# CH32F_V208C-R0.net
KiCad netlist of a schematic drawn in Altium Designer
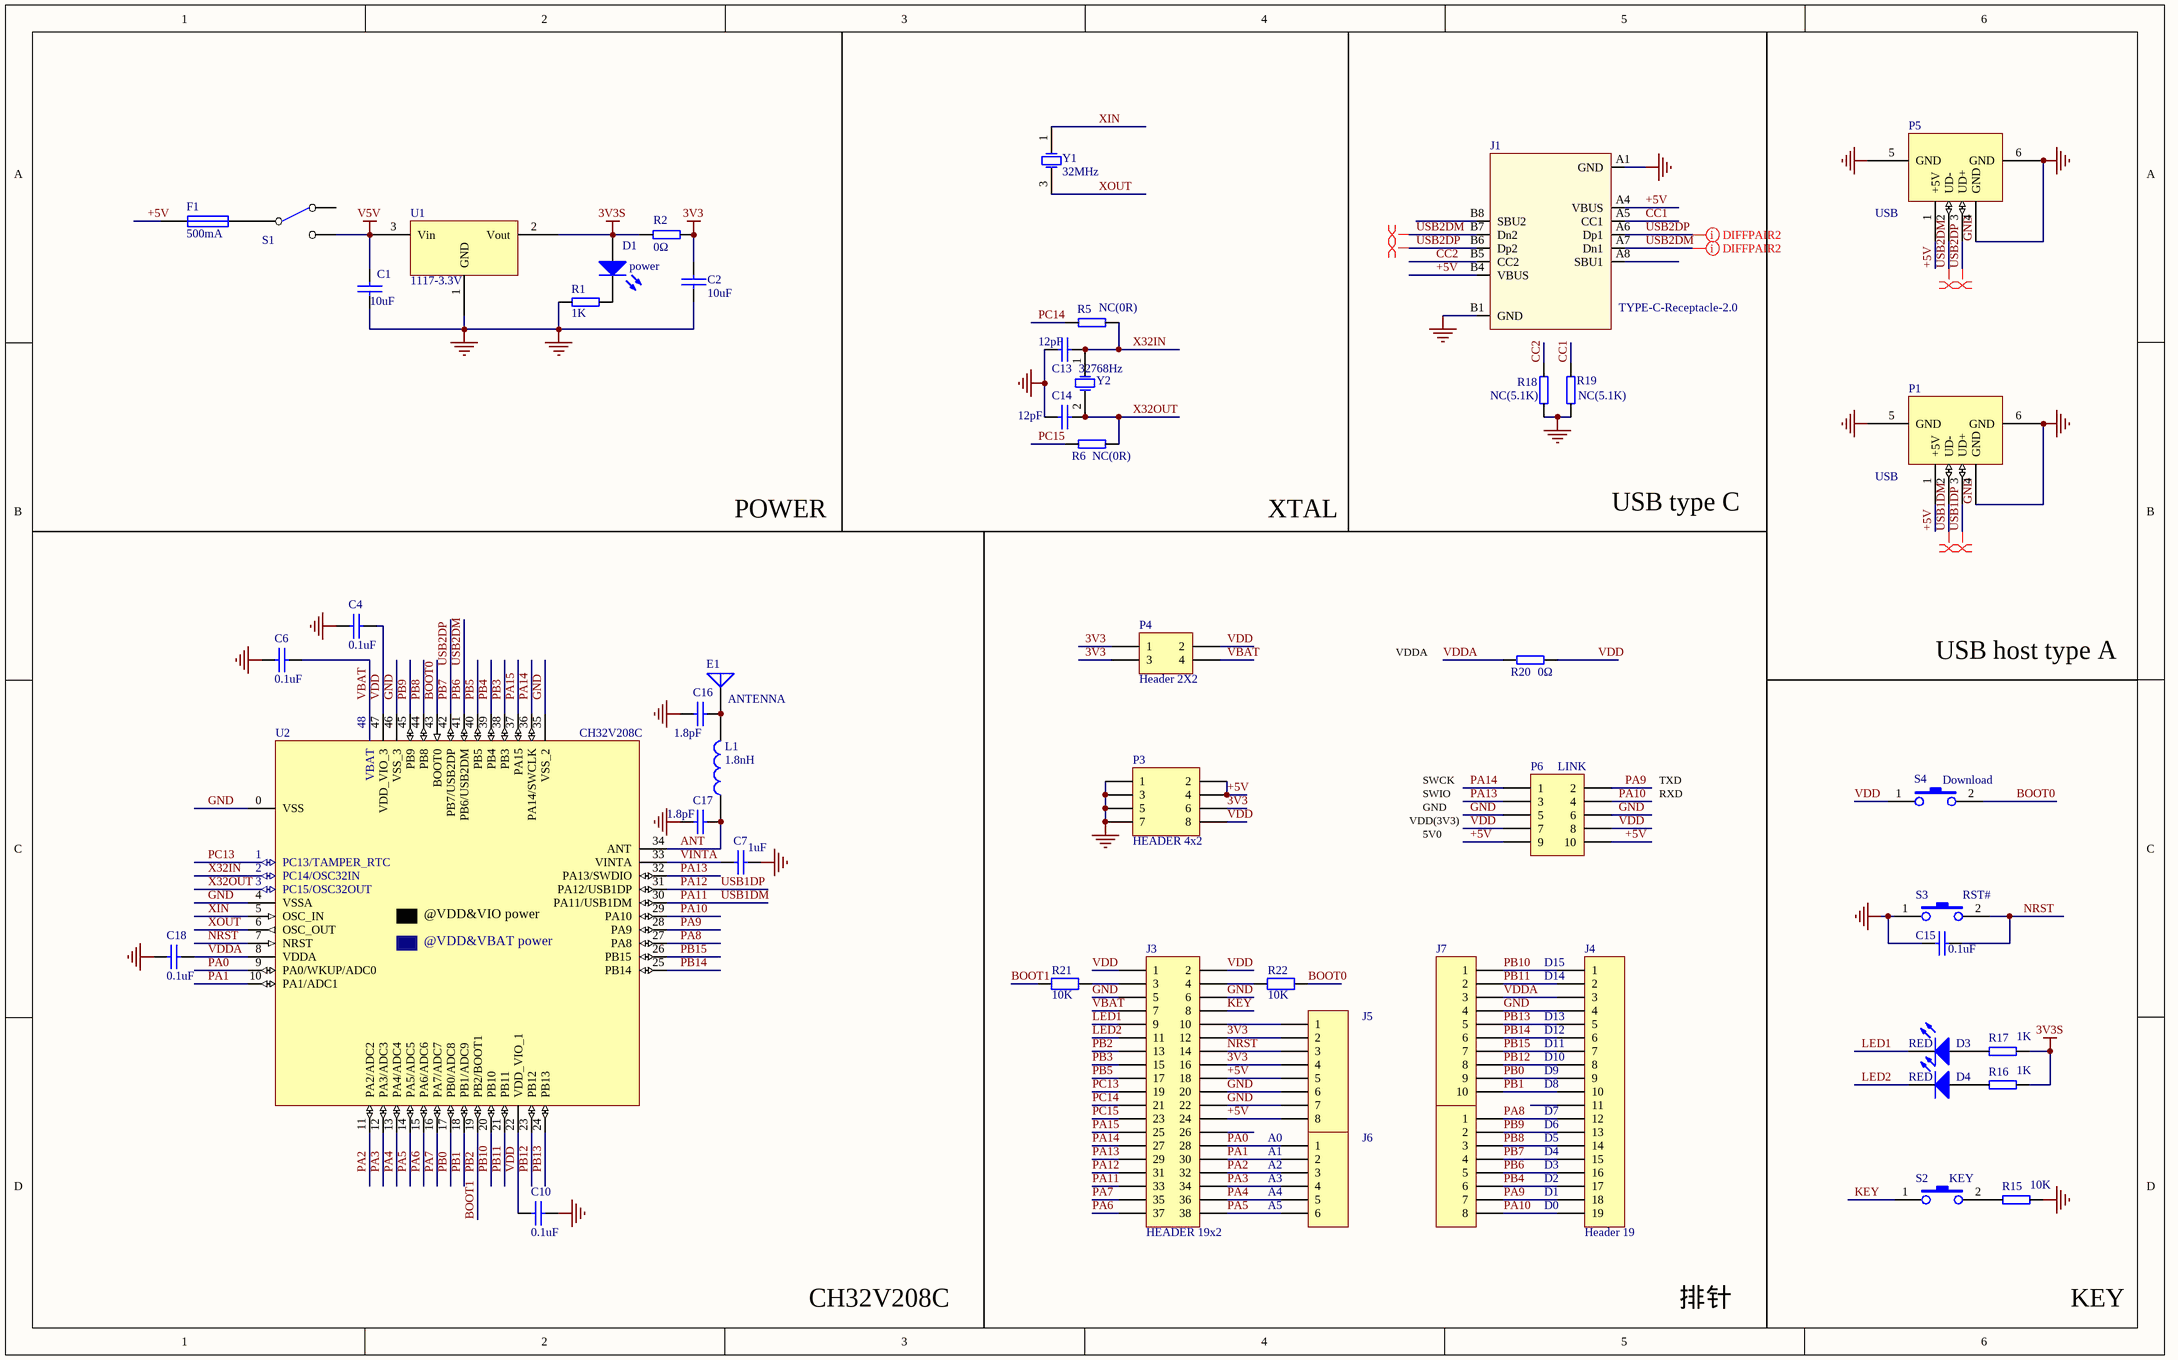
[diagram p0: CH32F&V208C-R0.SchDoc]

(export (version "E")
  (design (tool "Eeschema 10.0.6"))
  (components
    (comp (ref "C1")
      (value "10uF")
      (footprint "3216_C")
      (description "Capacitor")
      (libsource (lib "") (part "CAP_1"))
    )
    (comp (ref "C2")
      (value "10uF")
      (footprint "0603_C")
      (description "Capacitor")
      (libsource (lib "") (part "CAP_1"))
    )
    (comp (ref "C4")
      (value "0.1uF")
      (footprint "0603_C")
      (description "Capacitor")
      (libsource (lib "*") (part "CAP"))
    )
    (comp (ref "C6")
      (value "0.1uF")
      (footprint "0603_C")
      (description "Capacitor")
      (libsource (lib "*") (part "CAP"))
    )
    (comp (ref "C7")
      (value "1uF")
      (footprint "0603_C")
      (description "Capacitor")
      (libsource (lib "*") (part "CAP"))
    )
    (comp (ref "C10")
      (value "0.1uF")
      (footprint "0603_C")
      (description "Capacitor")
      (libsource (lib "*") (part "CAP"))
    )
    (comp (ref "C13")
      (value "12pF")
      (footprint "0603_C")
      (description "Capacitor")
      (libsource (lib "") (part "CAP_1"))
    )
    (comp (ref "C14")
      (value "12pF")
      (footprint "0603_C")
      (description "Capacitor")
      (libsource (lib "") (part "CAP_1"))
    )
    (comp (ref "C15")
      (value "0.1uF")
      (footprint "0603_C")
      (description "Capacitor")
      (libsource (lib "*") (part "CAP"))
    )
    (comp (ref "C16")
      (value "1.8pF")
      (footprint "0603_C")
      (description "Capacitor")
      (libsource (lib "*") (part "CAP"))
    )
    (comp (ref "C17")
      (value "1.8pF")
      (footprint "0603_C")
      (description "Capacitor")
      (libsource (lib "*") (part "CAP"))
    )
    (comp (ref "C18")
      (value "0.1uF")
      (footprint "0603_C")
      (description "Capacitor")
      (libsource (lib "*") (part "CAP"))
    )
    (comp (ref "D1")
      (value "power")
      (footprint "0603+")
      (description "Typical INFRARED GaAs LED")
      (fields (field (name "PUBLISHER") "Altium Limited"))
      (libsource (lib "*") (part "LED0"))
    )
    (comp (ref "D3")
      (value "RED")
      (footprint "0603+")
      (description "Typical INFRARED GaAs LED")
      (fields (field (name "PUBLISHER") "Altium Limited"))
      (libsource (lib "*") (part "LED0"))
    )
    (comp (ref "D4")
      (value "RED")
      (footprint "0603+")
      (description "Typical INFRARED GaAs LED")
      (fields (field (name "PUBLISHER") "Altium Limited"))
      (libsource (lib "*") (part "LED0"))
    )
    (comp (ref "E1")
      (value "ANTENNA")
      (footprint "ANT-F-1-2.4G-1.6mmFR4")
      (description "Generic Antenna")
      (libsource (lib "*") (part "ANTENNA"))
    )
    (comp (ref "F1")
      (value "500mA")
      (footprint "0603")
      (description "Fuse")
      (libsource (lib "wch_sch_others") (part "FUSE1"))
    )
    (comp (ref "J1")
      (value "TYPE-C-Receptacle-2.0")
      (footprint "TYPE-C-Receptacle-2.0")
      (description "Type-C USB2.0 母座")
      (libsource (lib "Miscellaneous SCH Lib") (part "TYPE-C-Receptacle-2.0"))
    )
    (comp (ref "J3")
      (value "HEADER 19x2")
      (footprint "MYPCB:IDC38-2.54MM")
      (description "Header, 19-Pin, Dual row")
      (libsource (lib "wch_sch_others") (part "HEADER 19x2"))
    )
    (comp (ref "J4")
      (value "Header 19")
      (footprint "SIP19-2.54mm")
      (description "Header, 19-Pin")
      (fields (field (name "PUBLISHER") "Altium Limited"))
      (libsource (lib "Miscellaneous Connectors") (part "Header 19"))
    )
    (comp (ref "J5")
      (value "Header 8")
      (footprint "SIP8-2.54mm")
      (description "Header, 8-Pin")
      (fields (field (name "PUBLISHER") "Altium Limited"))
      (libsource (lib "") (part "Header 8_1"))
    )
    (comp (ref "J6")
      (value "Header 6")
      (footprint "SIP6-2.54MM")
      (description "Header, 6-Pin")
      (fields (field (name "PUBLISHER") "Altium Limited"))
      (libsource (lib "Miscellaneous Connectors") (part "Header 6"))
    )
    (comp (ref "J7")
      (value "Header 10")
      (footprint "SIP10-2.54mm")
      (description "Header, 10-Pin")
      (fields (field (name "PUBLISHER") "Altium Limited"))
      (libsource (lib "Miscellaneous Connectors") (part "Header 10"))
    )
    (comp (ref "J8")
      (value "Header 8")
      (footprint "SIP8-2.54mm")
      (description "Header, 8-Pin")
      (fields (field (name "PUBLISHER") "Altium Limited"))
      (libsource (lib "Miscellaneous Connectors") (part "Header 8"))
    )
    (comp (ref "L1") (value "1.8nH") (footprint "0603") (libsource (lib "*") (part "INDUCTOR")))
    (comp (ref "P1")
      (value "USB")
      (footprint "USBAF")
      (description "USB Port")
      (libsource (lib "*") (part "USB"))
    )
    (comp (ref "P3")
      (value "HEADER 4x2")
      (footprint "MYPCB:IDC8-2.54mm")
      (description "Header, 4-Pin, Dual row")
      (libsource (lib "wch_sch_others") (part "HEADER 4x2"))
    )
    (comp (ref "P4")
      (value "Header 2X2")
      (footprint "IDC4-2.54mm")
      (description "Header, 2-Pin, Dual row")
      (fields (field (name "PUBLISHER") "Altium Limited"))
      (libsource (lib "Miscellaneous Connectors") (part "Header 2X2"))
    )
    (comp (ref "P5")
      (value "USB")
      (footprint "USBAF")
      (description "USB Port")
      (libsource (lib "*") (part "USB"))
    )
    (comp (ref "P6")
      (value "LINK")
      (footprint "IDC10-2.54mm")
      (description "Header, 5-Pin, Dual row, Right Angle")
      (fields (field (name "PUBLISHER") "Altium Limited"))
      (libsource (lib "Miscellaneous Connectors") (part "Header 5X2H"))
    )
    (comp (ref "R1") (value "1K") (footprint "0603") (libsource (lib "wch_sch_others") (part "RES")))
    (comp (ref "R2") (value "0Ω") (footprint "0603") (libsource (lib "wch_sch_others") (part "RES")))
    (comp (ref "R5") (value "NC(0R)") (footprint "0603") (libsource (lib "wch_sch_others") (part "RES")))
    (comp (ref "R6") (value "NC(0R)") (footprint "0603") (libsource (lib "wch_sch_others") (part "RES")))
    (comp (ref "R15") (value "10K") (footprint "0603") (libsource (lib "wch_sch_others") (part "RES")))
    (comp (ref "R16") (value "1K") (footprint "0603") (libsource (lib "wch_sch_others") (part "RES")))
    (comp (ref "R17") (value "1K") (footprint "0603") (libsource (lib "wch_sch_others") (part "RES")))
    (comp (ref "R18") (value "NC(5.1K)") (footprint "0603") (libsource (lib "wch_sch_others") (part "RES")))
    (comp (ref "R19") (value "NC(5.1K)") (footprint "0603") (libsource (lib "wch_sch_others") (part "RES")))
    (comp (ref "R20") (value "0Ω") (footprint "0603") (libsource (lib "*") (part "R")))
    (comp (ref "R21")
      (value "10K")
      (footprint "0603")
      (description "Resistor")
      (libsource (lib "Miscellaneous Devices") (part "Res2"))
    )
    (comp (ref "R22")
      (value "10K")
      (footprint "0603")
      (description "Resistor")
      (libsource (lib "Miscellaneous Devices") (part "Res2"))
    )
    (comp (ref "S1") (value "SW SPDT") (footprint "SW1") (libsource (lib "*") (part "SW SPDT")))
    (comp (ref "S2")
      (value "KEY")
      (footprint "SMD_6.1x3.65x2.5mm-KEY")
      (libsource (lib "wch_sch_others") (part "KEY1"))
    )
    (comp (ref "S3")
      (value "RST#")
      (footprint "SMD_6.1x3.65x2.5mm-KEY")
      (libsource (lib "wch_sch_others") (part "KEY1"))
    )
    (comp (ref "S4")
      (value "Download")
      (footprint "SMD_6.1x3.65x2.5mm-KEY")
      (libsource (lib "wch_sch_others") (part "KEY1"))
    )
    (comp (ref "U1")
      (value "1117-3.3V")
      (footprint "SOT-223")
      (libsource (lib "wch_sch_others") (part "1117-3.3V"))
    )
    (comp (ref "U2")
      (value "CH32V208C")
      (footprint "QFN48_5x5")
      (description "RISC-V BLE5.3 MCU, 10M Ethernet, 2*USB, CAN")
      (libsource (lib "CHXXX") (part "CH32V208C"))
    )
    (comp (ref "Y1")
      (value "32MHz")
      (footprint "XT3225")
      (description "Crystal Oscillator")
      (fields (field (name "PUBLISHER") "Altium Limited"))
      (libsource (lib "") (part "XTAL_1"))
    )
    (comp (ref "Y2")
      (value "32768Hz")
      (footprint "FC-135")
      (description "Crystal Oscillator")
      (fields (field (name "PUBLISHER") "Altium Limited"))
      (libsource (lib "*") (part "XTAL"))
    )
  )
  (nets
    (net (code "1") (name "/+5V") (class "Default")
      (node (ref "F1") (pin "1") (pinfunction "1_1") (pintype "passive"))
      (node (ref "J1") (pin "A4") (pinfunction "VBUS_A4") (pintype "passive"))
      (node (ref "J1") (pin "B4") (pinfunction "VBUS_B4") (pintype "passive"))
      (node (ref "J3") (pin "18") (pinfunction "18_18") (pintype "passive"))
      (node (ref "J3") (pin "24") (pinfunction "24_24") (pintype "passive"))
      (node (ref "J5") (pin "5") (pinfunction "5_5") (pintype "passive"))
      (node (ref "J5") (pin "8") (pinfunction "8_8") (pintype "passive"))
      (node (ref "P1") (pin "1") (pinfunction "+5V_1") (pintype "power_in"))
      (node (ref "P3") (pin "2") (pinfunction "2_2") (pintype "passive"))
      (node (ref "P3") (pin "4") (pinfunction "4_4") (pintype "passive"))
      (node (ref "P5") (pin "1") (pinfunction "+5V_1") (pintype "power_in"))
      (node (ref "P6") (pin "10") (pinfunction "10_10") (pintype "passive"))
      (node (ref "P6") (pin "9") (pinfunction "9_9") (pintype "passive"))
    )
    (net (code "2") (name "/ANT") (class "Default")
      (node (ref "C17") (pin "2") (pinfunction "2_2") (pintype "passive"))
      (node (ref "L1") (pin "1") (pinfunction "1_1") (pintype "passive"))
      (node (ref "U2") (pin "34") (pinfunction "ANT_34") (pintype "power_in"))
    )
    (net (code "3") (name "/BOOT0") (class "Default")
      (node (ref "R22") (pin "2") (pinfunction "2_2") (pintype "passive"))
      (node (ref "S4") (pin "2") (pinfunction "2_2") (pintype "passive"))
      (node (ref "U2") (pin "43") (pinfunction "BOOT0_43") (pintype "input"))
    )
    (net (code "4") (name "/BOOT1") (class "Default")
      (node (ref "J3") (pin "13") (pinfunction "13_13") (pintype "passive"))
      (node (ref "R21") (pin "1") (pinfunction "1_1") (pintype "passive"))
      (node (ref "U2") (pin "19") (pinfunction "PB2/BOOT1_19") (pintype "bidirectional"))
    )
    (net (code "5") (name "/CC1") (class "Default")
      (node (ref "J1") (pin "A5") (pinfunction "CC1_A5") (pintype "passive"))
      (node (ref "R19") (pin "1") (pintype "passive"))
    )
    (net (code "6") (name "/CC2") (class "Default")
      (node (ref "J1") (pin "B5") (pinfunction "CC2_B5") (pintype "passive"))
      (node (ref "R18") (pin "1") (pintype "passive"))
    )
    (net (code "7") (name "/KEY") (class "Default")
      (node (ref "J3") (pin "8") (pinfunction "8_8") (pintype "passive"))
      (node (ref "S2") (pin "1") (pinfunction "1_1") (pintype "passive"))
    )
    (net (code "8") (name "/LED1") (class "Default")
      (node (ref "D3") (pin "2") (pinfunction "K_2") (pintype "passive"))
      (node (ref "J3") (pin "9") (pinfunction "9_9") (pintype "passive"))
    )
    (net (code "9") (name "/LED2") (class "Default")
      (node (ref "D4") (pin "2") (pinfunction "K_2") (pintype "passive"))
      (node (ref "J3") (pin "11") (pinfunction "11_11") (pintype "passive"))
    )
    (net (code "10") (name "/NRST") (class "Default")
      (node (ref "C15") (pin "2") (pinfunction "2_2") (pintype "passive"))
      (node (ref "J3") (pin "14") (pinfunction "14_14") (pintype "passive"))
      (node (ref "J5") (pin "3") (pinfunction "3_3") (pintype "passive"))
      (node (ref "S3") (pin "2") (pinfunction "2_2") (pintype "passive"))
      (node (ref "U2") (pin "7") (pinfunction "NRST_7") (pintype "input"))
    )
    (net (code "11") (name "/PA0") (class "Default")
      (node (ref "J3") (pin "28") (pinfunction "28_28") (pintype "passive"))
      (node (ref "J6") (pin "1") (pinfunction "1_1") (pintype "passive"))
      (node (ref "U2") (pin "9") (pinfunction "PA0/WKUP/ADC0_9") (pintype "bidirectional"))
    )
    (net (code "12") (name "/PA1") (class "Default")
      (node (ref "J3") (pin "30") (pinfunction "30_30") (pintype "passive"))
      (node (ref "J6") (pin "2") (pinfunction "2_2") (pintype "passive"))
      (node (ref "U2") (pin "10") (pinfunction "PA1/ADC1_10") (pintype "bidirectional"))
    )
    (net (code "13") (name "/PA2") (class "Default")
      (node (ref "J3") (pin "32") (pinfunction "32_32") (pintype "passive"))
      (node (ref "J6") (pin "3") (pinfunction "3_3") (pintype "passive"))
      (node (ref "U2") (pin "11") (pinfunction "PA2/ADC2_11") (pintype "bidirectional"))
    )
    (net (code "14") (name "/PA3") (class "Default")
      (node (ref "J3") (pin "34") (pinfunction "34_34") (pintype "passive"))
      (node (ref "J6") (pin "4") (pinfunction "4_4") (pintype "passive"))
      (node (ref "U2") (pin "12") (pinfunction "PA3/ADC3_12") (pintype "bidirectional"))
    )
    (net (code "15") (name "/PA4") (class "Default")
      (node (ref "J3") (pin "36") (pinfunction "36_36") (pintype "passive"))
      (node (ref "J6") (pin "5") (pinfunction "5_5") (pintype "passive"))
      (node (ref "U2") (pin "13") (pinfunction "PA4/ADC4_13") (pintype "bidirectional"))
    )
    (net (code "16") (name "/PA5") (class "Default")
      (node (ref "J3") (pin "38") (pinfunction "38_38") (pintype "passive"))
      (node (ref "J6") (pin "6") (pinfunction "6_6") (pintype "passive"))
      (node (ref "U2") (pin "14") (pinfunction "PA5/ADC5_14") (pintype "bidirectional"))
    )
    (net (code "17") (name "/PA6") (class "Default")
      (node (ref "J3") (pin "37") (pinfunction "37_37") (pintype "passive"))
      (node (ref "U2") (pin "15") (pinfunction "PA6/ADC6_15") (pintype "bidirectional"))
    )
    (net (code "18") (name "/PA7") (class "Default")
      (node (ref "J3") (pin "35") (pinfunction "35_35") (pintype "passive"))
      (node (ref "U2") (pin "16") (pinfunction "PA7/ADC7_16") (pintype "bidirectional"))
    )
    (net (code "19") (name "/PA8") (class "Default")
      (node (ref "J4") (pin "12") (pinfunction "12_12") (pintype "passive"))
      (node (ref "J8") (pin "1") (pinfunction "1_1") (pintype "passive"))
      (node (ref "U2") (pin "27") (pinfunction "PA8_27") (pintype "bidirectional"))
    )
    (net (code "20") (name "/PA9") (class "Default")
      (node (ref "J4") (pin "18") (pinfunction "18_18") (pintype "passive"))
      (node (ref "J8") (pin "7") (pinfunction "7_7") (pintype "passive"))
      (node (ref "P6") (pin "2") (pinfunction "2_2") (pintype "passive"))
      (node (ref "U2") (pin "28") (pinfunction "PA9_28") (pintype "bidirectional"))
    )
    (net (code "21") (name "/PA10") (class "Default")
      (node (ref "J4") (pin "19") (pinfunction "19_19") (pintype "passive"))
      (node (ref "J8") (pin "8") (pinfunction "8_8") (pintype "passive"))
      (node (ref "P6") (pin "4") (pinfunction "4_4") (pintype "passive"))
      (node (ref "U2") (pin "29") (pinfunction "PA10_29") (pintype "bidirectional"))
    )
    (net (code "22") (name "/PA11") (class "Default")
      (node (ref "J3") (pin "33") (pinfunction "33_33") (pintype "passive"))
      (node (ref "P1") (pin "2") (pinfunction "UD-_2") (pintype "bidirectional"))
      (node (ref "U2") (pin "30") (pinfunction "PA11/USB1DM_30") (pintype "bidirectional"))
    )
    (net (code "23") (name "/PA12") (class "Default")
      (node (ref "J3") (pin "31") (pinfunction "31_31") (pintype "passive"))
      (node (ref "P1") (pin "3") (pinfunction "UD+_3") (pintype "bidirectional"))
      (node (ref "U2") (pin "31") (pinfunction "PA12/USB1DP_31") (pintype "bidirectional"))
    )
    (net (code "24") (name "/PA13") (class "Default")
      (node (ref "J3") (pin "29") (pinfunction "29_29") (pintype "passive"))
      (node (ref "P6") (pin "3") (pinfunction "3_3") (pintype "passive"))
      (node (ref "U2") (pin "32") (pinfunction "PA13/SWDIO_32") (pintype "bidirectional"))
    )
    (net (code "25") (name "/PA14") (class "Default")
      (node (ref "J3") (pin "27") (pinfunction "27_27") (pintype "passive"))
      (node (ref "P6") (pin "1") (pinfunction "1_1") (pintype "passive"))
      (node (ref "U2") (pin "36") (pinfunction "PA14/SWCLK_36") (pintype "bidirectional"))
    )
    (net (code "26") (name "/PA15") (class "Default")
      (node (ref "J3") (pin "25") (pinfunction "25_25") (pintype "passive"))
      (node (ref "U2") (pin "37") (pinfunction "PA15_37") (pintype "bidirectional"))
    )
    (net (code "27") (name "/PB0") (class "Default")
      (node (ref "J4") (pin "9") (pinfunction "9_9") (pintype "passive"))
      (node (ref "J7") (pin "9") (pinfunction "9_9") (pintype "passive"))
      (node (ref "U2") (pin "17") (pinfunction "PB0/ADC8_17") (pintype "bidirectional"))
    )
    (net (code "28") (name "/PB1") (class "Default")
      (node (ref "J4") (pin "10") (pinfunction "10_10") (pintype "passive"))
      (node (ref "J7") (pin "10") (pinfunction "10_10") (pintype "passive"))
      (node (ref "U2") (pin "18") (pinfunction "PB1/ADC9_18") (pintype "bidirectional"))
    )
    (net (code "29") (name "/PB3") (class "Default")
      (node (ref "J3") (pin "15") (pinfunction "15_15") (pintype "passive"))
      (node (ref "U2") (pin "38") (pinfunction "PB3_38") (pintype "bidirectional"))
    )
    (net (code "30") (name "/PB4") (class "Default")
      (node (ref "J4") (pin "17") (pinfunction "17_17") (pintype "passive"))
      (node (ref "J8") (pin "6") (pinfunction "6_6") (pintype "passive"))
      (node (ref "U2") (pin "39") (pinfunction "PB4_39") (pintype "bidirectional"))
    )
    (net (code "31") (name "/PB5") (class "Default")
      (node (ref "J3") (pin "17") (pinfunction "17_17") (pintype "passive"))
      (node (ref "U2") (pin "40") (pinfunction "PB5_40") (pintype "bidirectional"))
    )
    (net (code "32") (name "/PB6") (class "Default")
      (node (ref "J1") (pin "A7") (pinfunction "Dn1_A7") (pintype "passive"))
      (node (ref "J1") (pin "B7") (pinfunction "Dn2_B7") (pintype "passive"))
      (node (ref "J4") (pin "16") (pinfunction "16_16") (pintype "passive"))
      (node (ref "J8") (pin "5") (pinfunction "5_5") (pintype "passive"))
      (node (ref "P5") (pin "2") (pinfunction "UD-_2") (pintype "bidirectional"))
      (node (ref "U2") (pin "41") (pinfunction "PB6/USB2DM_41") (pintype "bidirectional"))
    )
    (net (code "33") (name "/PB7") (class "Default")
      (node (ref "J1") (pin "A6") (pinfunction "Dp1_A6") (pintype "passive"))
      (node (ref "J1") (pin "B6") (pinfunction "Dp2_B6") (pintype "passive"))
      (node (ref "J4") (pin "15") (pinfunction "15_15") (pintype "passive"))
      (node (ref "J8") (pin "4") (pinfunction "4_4") (pintype "passive"))
      (node (ref "P5") (pin "3") (pinfunction "UD+_3") (pintype "bidirectional"))
      (node (ref "U2") (pin "42") (pinfunction "PB7/USB2DP_42") (pintype "bidirectional"))
    )
    (net (code "34") (name "/PB8") (class "Default")
      (node (ref "J4") (pin "14") (pinfunction "14_14") (pintype "passive"))
      (node (ref "J8") (pin "3") (pinfunction "3_3") (pintype "passive"))
      (node (ref "U2") (pin "44") (pinfunction "PB8_44") (pintype "bidirectional"))
    )
    (net (code "35") (name "/PB9") (class "Default")
      (node (ref "J4") (pin "13") (pinfunction "13_13") (pintype "passive"))
      (node (ref "J8") (pin "2") (pinfunction "2_2") (pintype "passive"))
      (node (ref "U2") (pin "45") (pinfunction "PB9_45") (pintype "bidirectional"))
    )
    (net (code "36") (name "/PB10") (class "Default")
      (node (ref "J4") (pin "1") (pinfunction "1_1") (pintype "passive"))
      (node (ref "J7") (pin "1") (pinfunction "1_1") (pintype "passive"))
      (node (ref "U2") (pin "20") (pinfunction "PB10_20") (pintype "bidirectional"))
    )
    (net (code "37") (name "/PB11") (class "Default")
      (node (ref "J4") (pin "2") (pinfunction "2_2") (pintype "passive"))
      (node (ref "J7") (pin "2") (pinfunction "2_2") (pintype "passive"))
      (node (ref "U2") (pin "21") (pinfunction "PB11_21") (pintype "bidirectional"))
    )
    (net (code "38") (name "/PB12") (class "Default")
      (node (ref "J4") (pin "8") (pinfunction "8_8") (pintype "passive"))
      (node (ref "J7") (pin "8") (pinfunction "8_8") (pintype "passive"))
      (node (ref "U2") (pin "23") (pinfunction "PB12_23") (pintype "bidirectional"))
    )
    (net (code "39") (name "/PB13") (class "Default")
      (node (ref "J4") (pin "5") (pinfunction "5_5") (pintype "passive"))
      (node (ref "J7") (pin "5") (pinfunction "5_5") (pintype "passive"))
      (node (ref "U2") (pin "24") (pinfunction "PB13_24") (pintype "bidirectional"))
    )
    (net (code "40") (name "/PB14") (class "Default")
      (node (ref "J4") (pin "6") (pinfunction "6_6") (pintype "passive"))
      (node (ref "J7") (pin "6") (pinfunction "6_6") (pintype "passive"))
      (node (ref "U2") (pin "25") (pinfunction "PB14_25") (pintype "bidirectional"))
    )
    (net (code "41") (name "/PB15") (class "Default")
      (node (ref "J4") (pin "7") (pinfunction "7_7") (pintype "passive"))
      (node (ref "J7") (pin "7") (pinfunction "7_7") (pintype "passive"))
      (node (ref "U2") (pin "26") (pinfunction "PB15_26") (pintype "bidirectional"))
    )
    (net (code "42") (name "/PC13") (class "Default")
      (node (ref "J3") (pin "19") (pinfunction "19_19") (pintype "passive"))
      (node (ref "U2") (pin "1") (pinfunction "PC13/TAMPER_RTC_1") (pintype "bidirectional"))
    )
    (net (code "43") (name "/PC14") (class "Default")
      (node (ref "J3") (pin "21") (pinfunction "21_21") (pintype "passive"))
      (node (ref "R5") (pin "1") (pintype "passive"))
    )
    (net (code "44") (name "/PC15") (class "Default")
      (node (ref "J3") (pin "23") (pinfunction "23_23") (pintype "passive"))
      (node (ref "R6") (pin "1") (pintype "passive"))
    )
    (net (code "45") (name "/VBAT") (class "Default")
      (node (ref "C6") (pin "1") (pinfunction "1_1") (pintype "passive"))
      (node (ref "J3") (pin "7") (pinfunction "7_7") (pintype "passive"))
      (node (ref "P4") (pin "4") (pinfunction "4_4") (pintype "passive"))
      (node (ref "U2") (pin "48") (pinfunction "VBAT_48") (pintype "power_in"))
    )
    (net (code "46") (name "/VDD") (class "Default")
      (node (ref "C10") (pin "2") (pinfunction "2_2") (pintype "passive"))
      (node (ref "C4") (pin "1") (pinfunction "1_1") (pintype "passive"))
      (node (ref "J3") (pin "1") (pinfunction "1_1") (pintype "passive"))
      (node (ref "J3") (pin "2") (pinfunction "2_2") (pintype "passive"))
      (node (ref "P3") (pin "8") (pinfunction "8_8") (pintype "passive"))
      (node (ref "P4") (pin "2") (pinfunction "2_2") (pintype "passive"))
      (node (ref "P6") (pin "7") (pinfunction "7_7") (pintype "passive"))
      (node (ref "P6") (pin "8") (pinfunction "8_8") (pintype "passive"))
      (node (ref "R20") (pin "1") (pinfunction "1_1") (pintype "passive"))
      (node (ref "S4") (pin "1") (pinfunction "1_1") (pintype "passive"))
      (node (ref "U2") (pin "22") (pinfunction "VDD_VIO_1_22") (pintype "power_in"))
      (node (ref "U2") (pin "47") (pinfunction "VDD_VIO_3_47") (pintype "power_in"))
    )
    (net (code "47") (name "/VDDA") (class "Default")
      (node (ref "C18") (pin "1") (pinfunction "1_1") (pintype "passive"))
      (node (ref "J4") (pin "3") (pinfunction "3_3") (pintype "passive"))
      (node (ref "J7") (pin "3") (pinfunction "3_3") (pintype "passive"))
      (node (ref "R20") (pin "2") (pinfunction "2_2") (pintype "passive"))
      (node (ref "U2") (pin "8") (pinfunction "VDDA_8") (pintype "power_in"))
    )
    (net (code "48") (name "/VINTA") (class "Default")
      (node (ref "C7") (pin "1") (pinfunction "1_1") (pintype "passive"))
      (node (ref "U2") (pin "33") (pinfunction "VINTA_33") (pintype "power_in"))
    )
    (net (code "49") (name "/X32IN") (class "Default")
      (node (ref "C13") (pin "2") (pinfunction "2_2") (pintype "passive"))
      (node (ref "R5") (pin "2") (pintype "passive"))
      (node (ref "U2") (pin "2") (pinfunction "PC14/OSC32IN_2") (pintype "bidirectional"))
      (node (ref "Y2") (pin "1") (pinfunction "OSC1_1") (pintype "passive"))
    )
    (net (code "50") (name "/X32OUT") (class "Default")
      (node (ref "C14") (pin "2") (pinfunction "2_2") (pintype "passive"))
      (node (ref "R6") (pin "2") (pintype "passive"))
      (node (ref "U2") (pin "3") (pinfunction "PC15/OSC32OUT_3") (pintype "bidirectional"))
      (node (ref "Y2") (pin "2") (pinfunction "OSC2_2") (pintype "passive"))
    )
    (net (code "51") (name "/XIN") (class "Default")
      (node (ref "U2") (pin "5") (pinfunction "OSC_IN_5") (pintype "input"))
      (node (ref "Y1") (pin "1") (pinfunction "OSC1_1") (pintype "passive"))
    )
    (net (code "52") (name "/XOUT") (class "Default")
      (node (ref "U2") (pin "6") (pinfunction "OSC_OUT_6") (pintype "output"))
      (node (ref "Y1") (pin "3") (pinfunction "OSC2_3") (pintype "passive"))
    )
    (net (code "53") (name "3V3") (class "Default")
      (node (ref "C2") (pin "1") (pinfunction "1_1") (pintype "passive"))
      (node (ref "J3") (pin "12") (pinfunction "12_12") (pintype "passive"))
      (node (ref "J3") (pin "16") (pinfunction "16_16") (pintype "passive"))
      (node (ref "J5") (pin "2") (pinfunction "2_2") (pintype "passive"))
      (node (ref "J5") (pin "4") (pinfunction "4_4") (pintype "passive"))
      (node (ref "P3") (pin "6") (pinfunction "6_6") (pintype "passive"))
      (node (ref "P4") (pin "1") (pinfunction "1_1") (pintype "passive"))
      (node (ref "P4") (pin "3") (pinfunction "3_3") (pintype "passive"))
      (node (ref "R2") (pin "1") (pintype "passive"))
    )
    (net (code "54") (name "3V3S") (class "Default")
      (node (ref "D1") (pin "1") (pinfunction "A_1") (pintype "passive"))
      (node (ref "R16") (pin "1") (pintype "passive"))
      (node (ref "R17") (pin "1") (pintype "passive"))
      (node (ref "R2") (pin "2") (pintype "passive"))
      (node (ref "U1") (pin "2") (pinfunction "Vout_2") (pintype "passive"))
    )
    (net (code "55") (name "GND") (class "Default")
      (node (ref "C1") (pin "2") (pinfunction "2_2") (pintype "passive"))
      (node (ref "C10") (pin "1") (pinfunction "1_1") (pintype "passive"))
      (node (ref "C13") (pin "1") (pinfunction "1_1") (pintype "passive"))
      (node (ref "C14") (pin "1") (pinfunction "1_1") (pintype "passive"))
      (node (ref "C15") (pin "1") (pinfunction "1_1") (pintype "passive"))
      (node (ref "C16") (pin "1") (pinfunction "1_1") (pintype "passive"))
      (node (ref "C17") (pin "1") (pinfunction "1_1") (pintype "passive"))
      (node (ref "C18") (pin "2") (pinfunction "2_2") (pintype "passive"))
      (node (ref "C2") (pin "2") (pinfunction "2_2") (pintype "passive"))
      (node (ref "C4") (pin "2") (pinfunction "2_2") (pintype "passive"))
      (node (ref "C6") (pin "2") (pinfunction "2_2") (pintype "passive"))
      (node (ref "C7") (pin "2") (pinfunction "2_2") (pintype "passive"))
      (node (ref "J1") (pin "A1") (pinfunction "GND_A1") (pintype "passive"))
      (node (ref "J1") (pin "B1") (pinfunction "GND_B1") (pintype "passive"))
      (node (ref "J3") (pin "20") (pinfunction "20_20") (pintype "passive"))
      (node (ref "J3") (pin "22") (pinfunction "22_22") (pintype "passive"))
      (node (ref "J3") (pin "5") (pinfunction "5_5") (pintype "passive"))
      (node (ref "J3") (pin "6") (pinfunction "6_6") (pintype "passive"))
      (node (ref "J4") (pin "4") (pinfunction "4_4") (pintype "passive"))
      (node (ref "J5") (pin "6") (pinfunction "6_6") (pintype "passive"))
      (node (ref "J5") (pin "7") (pinfunction "7_7") (pintype "passive"))
      (node (ref "J7") (pin "4") (pinfunction "4_4") (pintype "passive"))
      (node (ref "P1") (pin "4") (pinfunction "GND_4") (pintype "power_in"))
      (node (ref "P1") (pin "5") (pinfunction "GND_5") (pintype "power_in"))
      (node (ref "P1") (pin "6") (pinfunction "GND_6") (pintype "power_in"))
      (node (ref "P3") (pin "1") (pinfunction "1_1") (pintype "passive"))
      (node (ref "P3") (pin "3") (pinfunction "3_3") (pintype "passive"))
      (node (ref "P3") (pin "5") (pinfunction "5_5") (pintype "passive"))
      (node (ref "P3") (pin "7") (pinfunction "7_7") (pintype "passive"))
      (node (ref "P5") (pin "4") (pinfunction "GND_4") (pintype "power_in"))
      (node (ref "P5") (pin "5") (pinfunction "GND_5") (pintype "power_in"))
      (node (ref "P5") (pin "6") (pinfunction "GND_6") (pintype "power_in"))
      (node (ref "P6") (pin "5") (pinfunction "5_5") (pintype "passive"))
      (node (ref "P6") (pin "6") (pinfunction "6_6") (pintype "passive"))
      (node (ref "R1") (pin "1") (pintype "passive"))
      (node (ref "R15") (pin "1") (pintype "passive"))
      (node (ref "R18") (pin "2") (pintype "passive"))
      (node (ref "R19") (pin "2") (pintype "passive"))
      (node (ref "S3") (pin "1") (pinfunction "1_1") (pintype "passive"))
      (node (ref "U1") (pin "1") (pinfunction "GND_1") (pintype "passive"))
      (node (ref "U2") (pin "0") (pinfunction "VSS_0") (pintype "power_in"))
      (node (ref "U2") (pin "35") (pinfunction "VSS_2_35") (pintype "power_in"))
      (node (ref "U2") (pin "4") (pinfunction "VSSA_4") (pintype "power_in"))
      (node (ref "U2") (pin "46") (pinfunction "VSS_3_46") (pintype "power_in"))
    )
    (net (code "56") (name "Net-(D1-K)") (class "Default")
      (node (ref "D1") (pin "2") (pinfunction "K_2") (pintype "passive"))
      (node (ref "R1") (pin "2") (pintype "passive"))
    )
    (net (code "57") (name "Net-(D3-A)") (class "Default")
      (node (ref "D3") (pin "1") (pinfunction "A_1") (pintype "passive"))
      (node (ref "R17") (pin "2") (pintype "passive"))
    )
    (net (code "58") (name "Net-(D4-A)") (class "Default")
      (node (ref "D4") (pin "1") (pinfunction "A_1") (pintype "passive"))
      (node (ref "R16") (pin "2") (pintype "passive"))
    )
    (net (code "59") (name "Net-(E1-A)") (class "Default")
      (node (ref "C16") (pin "2") (pinfunction "2_2") (pintype "passive"))
      (node (ref "E1") (pin "1") (pinfunction "A_1") (pintype "passive"))
      (node (ref "L1") (pin "2") (pinfunction "2_2") (pintype "passive"))
    )
    (net (code "60") (name "Net-(J3-Pad3)") (class "Default")
      (node (ref "J3") (pin "3") (pinfunction "3_3") (pintype "passive"))
      (node (ref "R21") (pin "2") (pinfunction "2_2") (pintype "passive"))
    )
    (net (code "61") (name "Net-(J3-Pad4)") (class "Default")
      (node (ref "J3") (pin "4") (pinfunction "4_4") (pintype "passive"))
      (node (ref "R22") (pin "1") (pinfunction "1_1") (pintype "passive"))
    )
    (net (code "62") (name "Net-(J3-Pad10)") (class "Default")
      (node (ref "J3") (pin "10") (pinfunction "10_10") (pintype "passive"))
      (node (ref "J5") (pin "1") (pinfunction "1_1") (pintype "passive"))
    )
    (net (code "63") (name "Net-(R15-Pad2)") (class "Default")
      (node (ref "R15") (pin "2") (pintype "passive"))
      (node (ref "S2") (pin "2") (pinfunction "2_2") (pintype "passive"))
    )
    (net (code "64") (name "Net-(S1-COMMON)") (class "Default")
      (node (ref "F1") (pin "2") (pinfunction "2_2") (pintype "passive"))
      (node (ref "S1") (pin "1") (pinfunction "COMMON_1") (pintype "passive"))
    )
    (net (code "65") (name "V5V") (class "Default")
      (node (ref "C1") (pin "1") (pinfunction "1_1") (pintype "passive"))
      (node (ref "S1") (pin "2") (pinfunction "NC_2") (pintype "passive"))
      (node (ref "U1") (pin "3") (pinfunction "Vin_3") (pintype "passive"))
    )
    (net (code "66") (name "unconnected-(J1-SBU1-PadA8)") (class "Default")
      (node (ref "J1") (pin "A8") (pinfunction "SBU1_A8") (pintype "passive"))
    )
    (net (code "67") (name "unconnected-(J1-SBU2-PadB8)") (class "Default")
      (node (ref "J1") (pin "B8") (pinfunction "SBU2_B8") (pintype "passive"))
    )
    (net (code "68") (name "unconnected-(J3-Pad26)") (class "Default")
      (node (ref "J3") (pin "26") (pinfunction "26_26") (pintype "passive"))
    )
    (net (code "69") (name "unconnected-(J4-Pad11)") (class "Default")
      (node (ref "J4") (pin "11") (pinfunction "11_11") (pintype "passive"))
    )
    (net (code "70") (name "unconnected-(S1-NO-Pad3)") (class "Default")
      (node (ref "S1") (pin "3") (pinfunction "NO_3") (pintype "passive"))
    )
  )
)
